# SparkFun_MOSFET_Power_Switch.net
KiCad netlist of a schematic drawn in EAGLE
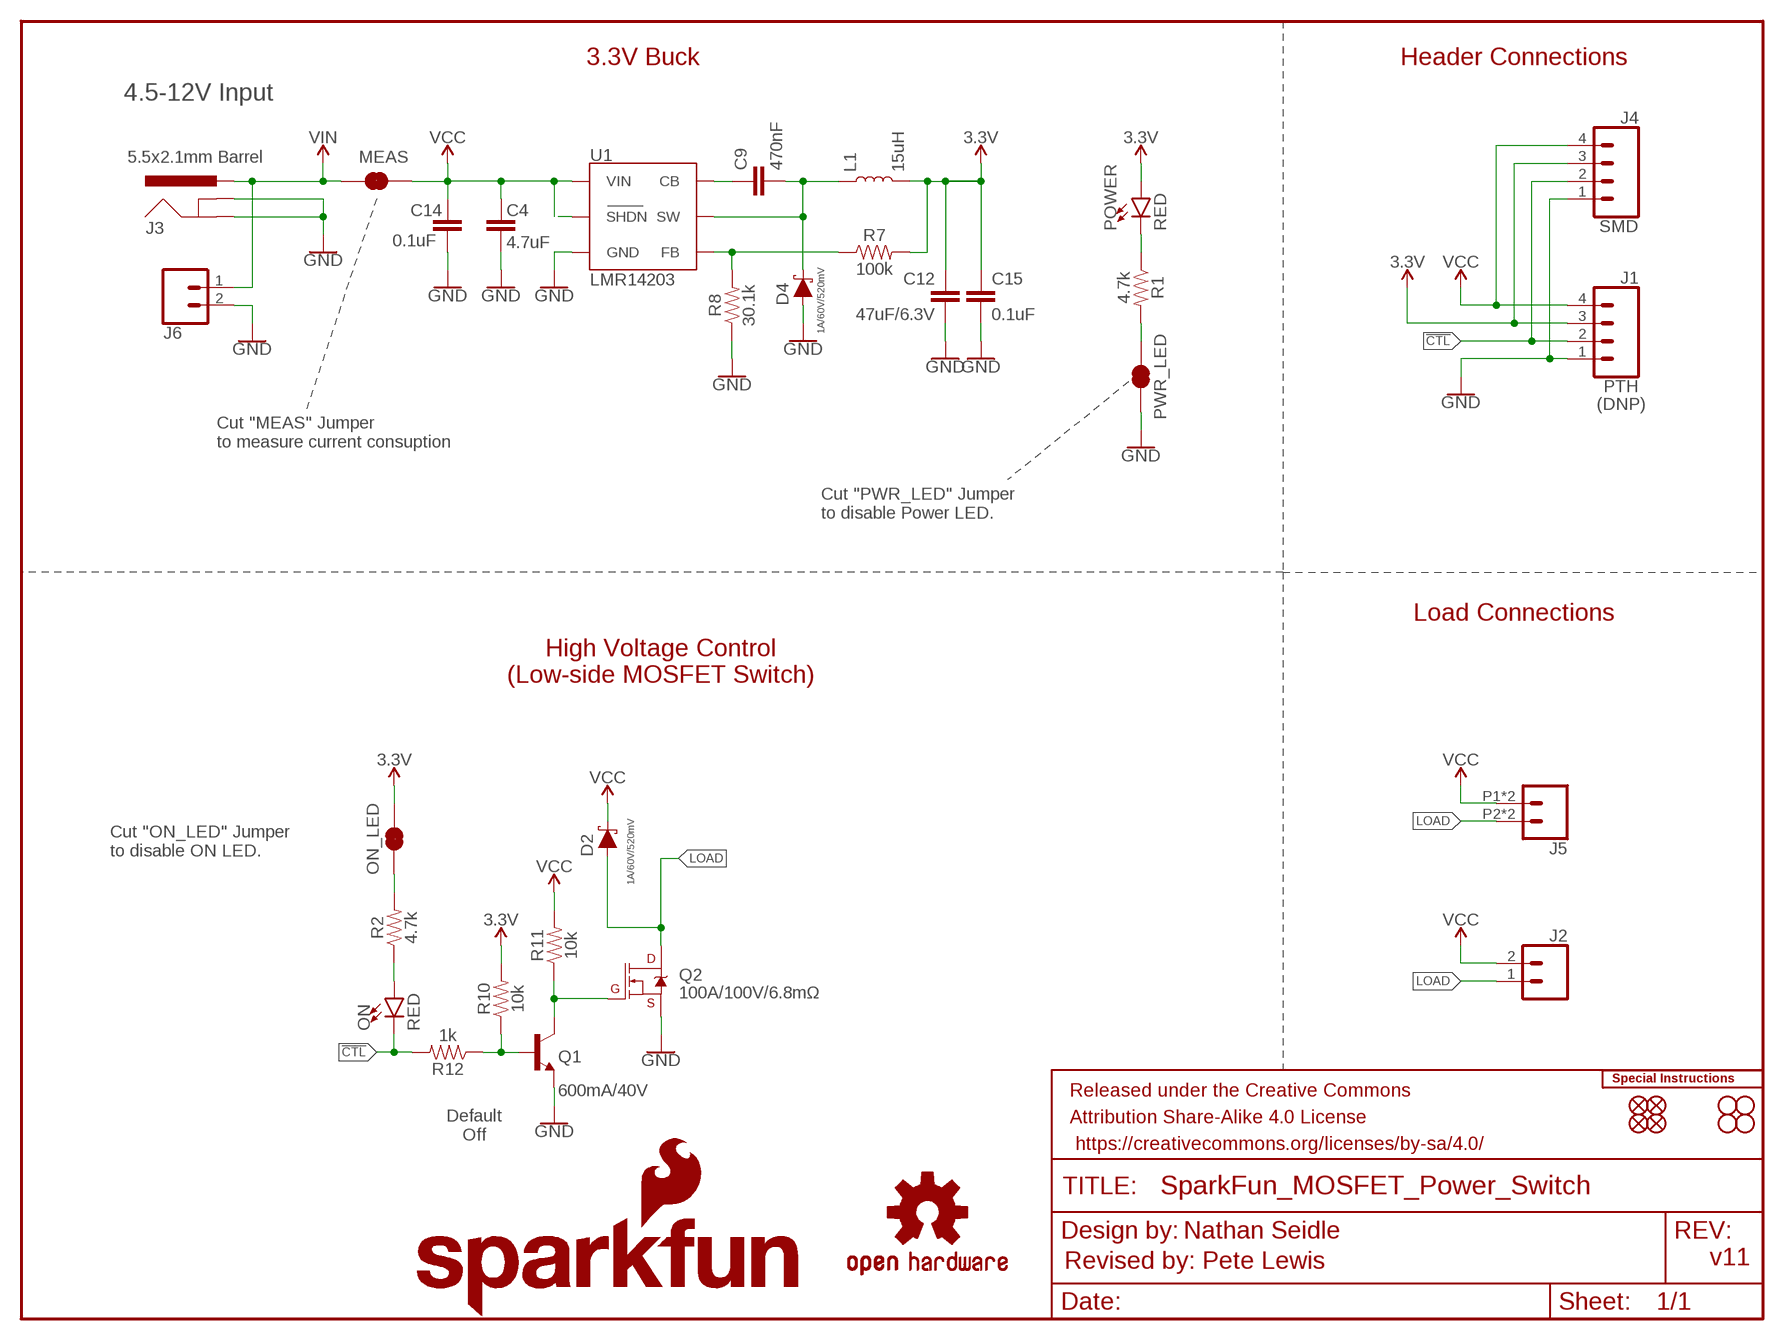
[diagram p0: schematic, sheet 1]

(export (version "E")
  (design (tool "Eeschema 10.0.6"))
  (components
    (comp (ref "C4")
      (value "4.7uF")
      (footprint "eagle-import:0603")
      (libsource (lib "eagle-import") (part "4.7UF-0603-35V-(20%)"))
    )
    (comp (ref "C9")
      (value "470nF")
      (footprint "eagle-import:0603")
      (libsource (lib "eagle-import") (part "470NF-0603-10V-10%-X5R"))
    )
    (comp (ref "C12")
      (value "47uF/6.3V")
      (footprint "eagle-import:0805")
      (libsource (lib "eagle-import") (part "47UF"))
    )
    (comp (ref "C14")
      (value "0.1uF")
      (footprint "eagle-import:0603")
      (libsource (lib "eagle-import") (part "0.1UF-0603-100V-10%"))
    )
    (comp (ref "C15")
      (value "0.1uF")
      (footprint "eagle-import:0603")
      (libsource (lib "eagle-import") (part "0.1UF-0603-100V-10%"))
    )
    (comp (ref "D2")
      (value "1A/60V/520mV")
      (footprint "eagle-import:DIODE-MICRO-SMP")
      (libsource (lib "eagle-import") (part "DIODE-SCHOTTKY-MSS1P6-M3/89A"))
    )
    (comp (ref "D4")
      (value "1A/60V/520mV")
      (footprint "eagle-import:DIODE-MICRO-SMP")
      (libsource (lib "eagle-import") (part "DIODE-SCHOTTKY-MSS1P6-M3/89A"))
    )
    (comp (ref "FD1")
      (value "FIDUCIALUFIDUCIAL")
      (footprint "eagle-import:FIDUCIAL-MICRO")
      (libsource (lib "eagle-import") (part "FIDUCIALUFIDUCIAL"))
    )
    (comp (ref "FD2")
      (value "FIDUCIALUFIDUCIAL")
      (footprint "eagle-import:FIDUCIAL-MICRO")
      (libsource (lib "eagle-import") (part "FIDUCIALUFIDUCIAL"))
    )
    (comp (ref "FD3")
      (value "FIDUCIALUFIDUCIAL")
      (footprint "eagle-import:FIDUCIAL-MICRO")
      (libsource (lib "eagle-import") (part "FIDUCIALUFIDUCIAL"))
    )
    (comp (ref "FD4")
      (value "FIDUCIALUFIDUCIAL")
      (footprint "eagle-import:FIDUCIAL-MICRO")
      (libsource (lib "eagle-import") (part "FIDUCIALUFIDUCIAL"))
    )
    (comp (ref "FRAME2")
      (value "FRAME-LETTER")
      (footprint "eagle-import:CREATIVE_COMMONS")
      (libsource (lib "eagle-import") (part "FRAME-LETTER"))
    )
    (comp (ref "H1")
      (value "STAND-OFF")
      (footprint "eagle-import:STAND-OFF")
      (libsource (lib "eagle-import") (part "STAND-OFF"))
    )
    (comp (ref "H2")
      (value "STAND-OFF")
      (footprint "eagle-import:STAND-OFF")
      (libsource (lib "eagle-import") (part "STAND-OFF"))
    )
    (comp (ref "H3")
      (value "STAND-OFF")
      (footprint "eagle-import:STAND-OFF")
      (libsource (lib "eagle-import") (part "STAND-OFF"))
    )
    (comp (ref "H4")
      (value "STAND-OFF")
      (footprint "eagle-import:STAND-OFF")
      (libsource (lib "eagle-import") (part "STAND-OFF"))
    )
    (comp (ref "J1")
      (value "PTH")
      (footprint "eagle-import:1X04_NO_SILK")
      (libsource (lib "eagle-import") (part "CONN_041X04_NO_SILK_NO_POP"))
    )
    (comp (ref "J2")
      (value "CONN_021X02_NO_SILK")
      (footprint "eagle-import:1X02_NO_SILK")
      (libsource (lib "eagle-import") (part "CONN_021X02_NO_SILK"))
    )
    (comp (ref "J3")
      (value "5.5x2.1mm Barrel")
      (footprint "eagle-import:POWER_JACK_SMD")
      (libsource (lib "eagle-import") (part "POWER_JACKSMD"))
    )
    (comp (ref "J4")
      (value "SMD")
      (footprint "eagle-import:1X04_SMD_VERTICAL_COMBO")
      (libsource (lib "eagle-import") (part "CONN_04SMD_STRAIGHT_COMBO"))
    )
    (comp (ref "J5")
      (value "CONN_02SMALL_POKEHOME")
      (footprint "eagle-import:1X02_POKEHOME")
      (libsource (lib "eagle-import") (part "CONN_02SMALL_POKEHOME"))
    )
    (comp (ref "J6")
      (value "CONN_021X02_NO_SILK")
      (footprint "eagle-import:1X02_NO_SILK")
      (libsource (lib "eagle-import") (part "CONN_021X02_NO_SILK"))
    )
    (comp (ref "L1")
      (value "15uH")
      (footprint "eagle-import:INDUCTOR_LQH32")
      (libsource (lib "eagle-import") (part "INDUCTOR-LHQ32-15UH"))
    )
    (comp (ref "LOGO1")
      (value "OSHW-LOGOM")
      (footprint "eagle-import:OSHW-LOGO-M")
      (libsource (lib "eagle-import") (part "OSHW-LOGOM"))
    )
    (comp (ref "LOGO2")
      (value "SFE_LOGO_NAME_FLAME.2_INCH")
      (footprint "eagle-import:SFE_LOGO_NAME_FLAME_.2")
      (libsource (lib "eagle-import") (part "SFE_LOGO_NAME_FLAME.2_INCH"))
    )
    (comp (ref "LOGO3")
      (value "SPECIAL_INSTRUCTIONS-ORDERING")
      (footprint "eagle-import:ORDERING_INSTRUCTIONS")
      (libsource (lib "eagle-import") (part "SPECIAL_INSTRUCTIONS-ORDERING"))
    )
    (comp (ref "MEAS")
      (value "JUMPER-COMBO_2_NC_TRACE")
      (footprint "eagle-import:COMBO-JUMPER_2_NC_TRACE")
      (libsource (lib "eagle-import") (part "JUMPER-COMBO_2_NC_TRACE"))
    )
    (comp (ref "ON")
      (value "RED")
      (footprint "eagle-import:LED-0603")
      (libsource (lib "eagle-import") (part "LED-RED_0603-KB"))
    )
    (comp (ref "ON_LED")
      (value "JUMPER-SMT_2_NC_TRACE_SILK")
      (footprint "eagle-import:SMT-JUMPER_2_NC_TRACE_SILK")
      (libsource (lib "eagle-import") (part "JUMPER-SMT_2_NC_TRACE_SILK"))
    )
    (comp (ref "POWER")
      (value "RED")
      (footprint "eagle-import:LED-0603")
      (libsource (lib "eagle-import") (part "LED-RED_0603-KB"))
    )
    (comp (ref "PWR_LED")
      (value "JUMPER-SMT_2_NC_TRACE_SILK")
      (footprint "eagle-import:SMT-JUMPER_2_NC_TRACE_SILK")
      (libsource (lib "eagle-import") (part "JUMPER-SMT_2_NC_TRACE_SILK"))
    )
    (comp (ref "Q1")
      (value "600mA/40V")
      (footprint "eagle-import:SOT23-3")
      (libsource (lib "eagle-import") (part "TRANS_NPN-MMBT2222AL"))
    )
    (comp (ref "Q2")
      (value "100A/100V/6.8mΩ")
      (footprint "eagle-import:TO-263_D2PAK")
      (libsource (lib "eagle-import") (part "MOSFET-NCH-PSMN7R0"))
    )
    (comp (ref "R1")
      (value "4.7k")
      (footprint "eagle-import:0603")
      (libsource (lib "eagle-import") (part "4.7KOHM-0603-1/10W-1%"))
    )
    (comp (ref "R2")
      (value "4.7k")
      (footprint "eagle-import:0603")
      (libsource (lib "eagle-import") (part "4.7KOHM-0603-1/10W-1%"))
    )
    (comp (ref "R7")
      (value "100k")
      (footprint "eagle-import:0603")
      (libsource (lib "eagle-import") (part "100KOHM-0603-1/10W-1%"))
    )
    (comp (ref "R8")
      (value "30.1k")
      (footprint "eagle-import:0603")
      (libsource (lib "eagle-import") (part "30.1KOHM-0603-1/10W-1%"))
    )
    (comp (ref "R10")
      (value "10k")
      (footprint "eagle-import:0603")
      (libsource (lib "eagle-import") (part "10KOHM-0603-1/10W-1%"))
    )
    (comp (ref "R11")
      (value "10k")
      (footprint "eagle-import:0603")
      (libsource (lib "eagle-import") (part "10KOHM-0603-1/10W-1%"))
    )
    (comp (ref "R12")
      (value "1k")
      (footprint "eagle-import:0603")
      (libsource (lib "eagle-import") (part "1KOHM-0603-1/10W-1%"))
    )
    (comp (ref "U1")
      (value "LMR14203")
      (footprint "eagle-import:SOT23-6")
      (libsource (lib "eagle-import") (part "LMR14203"))
    )
  )
  (nets
    (net (code "1") (name "/~{CTL}") (class "Default")
      (node (ref "J1") (pin "2") (pinfunction "2_2") (pintype "passive"))
      (node (ref "J4") (pin "2") (pinfunction "2_2") (pintype "passive"))
      (node (ref "ON") (pin "C") (pinfunction "C_C") (pintype "passive"))
      (node (ref "R12") (pin "2") (pinfunction "2_2") (pintype "passive"))
    )
    (net (code "2") (name "3.3V") (class "Default")
      (node (ref "C12") (pin "1") (pinfunction "1_1") (pintype "passive"))
      (node (ref "C15") (pin "1") (pinfunction "1_1") (pintype "passive"))
      (node (ref "J1") (pin "3") (pinfunction "3_3") (pintype "passive"))
      (node (ref "J4") (pin "3") (pinfunction "3_3") (pintype "passive"))
      (node (ref "L1") (pin "P$2") (pinfunction "2_P$2") (pintype "passive"))
      (node (ref "ON_LED") (pin "2") (pinfunction "2_2") (pintype "passive"))
      (node (ref "POWER") (pin "A") (pinfunction "A_A") (pintype "passive"))
      (node (ref "R10") (pin "2") (pinfunction "2_2") (pintype "passive"))
      (node (ref "R7") (pin "2") (pinfunction "2_2") (pintype "passive"))
    )
    (net (code "3") (name "GND") (class "Default")
      (node (ref "C12") (pin "2") (pinfunction "2_2") (pintype "passive"))
      (node (ref "C14") (pin "2") (pinfunction "2_2") (pintype "passive"))
      (node (ref "C15") (pin "2") (pinfunction "2_2") (pintype "passive"))
      (node (ref "C4") (pin "2") (pinfunction "2_2") (pintype "passive"))
      (node (ref "D4") (pin "A") (pinfunction "A_A") (pintype "passive"))
      (node (ref "J1") (pin "1") (pinfunction "1_1") (pintype "passive"))
      (node (ref "J3") (pin "GND") (pinfunction "GNDBREAK_GND") (pintype "bidirectional"))
      (node (ref "J3") (pin "P$4") (pinfunction "GND_P$4") (pintype "bidirectional"))
      (node (ref "J4") (pin "1") (pinfunction "1_1") (pintype "passive"))
      (node (ref "J6") (pin "2") (pinfunction "2_2") (pintype "passive"))
      (node (ref "PWR_LED") (pin "1") (pinfunction "1_1") (pintype "passive"))
      (node (ref "Q1") (pin "2") (pinfunction "E_2") (pintype "passive"))
      (node (ref "Q2") (pin "3") (pinfunction "S_3") (pintype "bidirectional"))
      (node (ref "R8") (pin "1") (pinfunction "1_1") (pintype "passive"))
      (node (ref "U1") (pin "2") (pinfunction "GND_2") (pintype "power_in"))
    )
    (net (code "4") (name "LOAD") (class "Default")
      (node (ref "D2") (pin "A") (pinfunction "A_A") (pintype "passive"))
      (node (ref "J2") (pin "1") (pinfunction "1_1") (pintype "passive"))
      (node (ref "J5") (pin "P2") (pinfunction "2_P2") (pintype "passive"))
      (node (ref "J5") (pin "P4") (pinfunction "2_P4") (pintype "passive"))
      (node (ref "Q2") (pin "2") (pinfunction "D_2") (pintype "bidirectional"))
    )
    (net (code "5") (name "Net-(L1-1)") (class "Default")
      (node (ref "C9") (pin "2") (pinfunction "2_2") (pintype "passive"))
      (node (ref "D4") (pin "C") (pinfunction "C_C") (pintype "passive"))
      (node (ref "L1") (pin "P$1") (pinfunction "1_P$1") (pintype "passive"))
      (node (ref "U1") (pin "6") (pinfunction "SW_6") (pintype "power_in"))
    )
    (net (code "6") (name "Net-(ON-PadA)") (class "Default")
      (node (ref "ON") (pin "A") (pinfunction "A_A") (pintype "passive"))
      (node (ref "R2") (pin "1") (pinfunction "1_1") (pintype "passive"))
    )
    (net (code "7") (name "Net-(ON_LED-Pad1)") (class "Default")
      (node (ref "ON_LED") (pin "1") (pinfunction "1_1") (pintype "passive"))
      (node (ref "R2") (pin "2") (pinfunction "2_2") (pintype "passive"))
    )
    (net (code "8") (name "Net-(POWER-PadC)") (class "Default")
      (node (ref "POWER") (pin "C") (pinfunction "C_C") (pintype "passive"))
      (node (ref "R1") (pin "1") (pinfunction "1_1") (pintype "passive"))
    )
    (net (code "9") (name "Net-(PWR_LED-Pad2)") (class "Default")
      (node (ref "PWR_LED") (pin "2") (pinfunction "2_2") (pintype "passive"))
      (node (ref "R1") (pin "2") (pinfunction "2_2") (pintype "passive"))
    )
    (net (code "10") (name "Net-(Q1-B)") (class "Default")
      (node (ref "Q1") (pin "1") (pinfunction "B_1") (pintype "passive"))
      (node (ref "R10") (pin "1") (pinfunction "1_1") (pintype "passive"))
      (node (ref "R12") (pin "1") (pinfunction "1_1") (pintype "passive"))
    )
    (net (code "11") (name "Net-(Q1-C)") (class "Default")
      (node (ref "Q1") (pin "3") (pinfunction "C_3") (pintype "passive"))
      (node (ref "Q2") (pin "1") (pinfunction "G_1") (pintype "bidirectional"))
      (node (ref "R11") (pin "1") (pinfunction "1_1") (pintype "passive"))
    )
    (net (code "12") (name "Net-(U1-CB)") (class "Default")
      (node (ref "C9") (pin "1") (pinfunction "1_1") (pintype "passive"))
      (node (ref "U1") (pin "1") (pinfunction "CB_1") (pintype "input"))
    )
    (net (code "13") (name "Net-(U1-FB)") (class "Default")
      (node (ref "R7") (pin "1") (pinfunction "1_1") (pintype "passive"))
      (node (ref "R8") (pin "2") (pinfunction "2_2") (pintype "passive"))
      (node (ref "U1") (pin "3") (pinfunction "FB_3") (pintype "input"))
    )
    (net (code "14") (name "VCC") (class "Default")
      (node (ref "C14") (pin "1") (pinfunction "1_1") (pintype "passive"))
      (node (ref "C4") (pin "1") (pinfunction "1_1") (pintype "passive"))
      (node (ref "D2") (pin "C") (pinfunction "C_C") (pintype "passive"))
      (node (ref "J1") (pin "4") (pinfunction "4_4") (pintype "passive"))
      (node (ref "J2") (pin "2") (pinfunction "2_2") (pintype "passive"))
      (node (ref "J4") (pin "4") (pinfunction "4_4") (pintype "passive"))
      (node (ref "J5") (pin "P1") (pinfunction "1_P1") (pintype "passive"))
      (node (ref "J5") (pin "P3") (pinfunction "1_P3") (pintype "passive"))
      (node (ref "MEAS") (pin "2") (pinfunction "2_2") (pintype "passive"))
      (node (ref "MEAS") (pin "4") (pinfunction "2_4") (pintype "passive"))
      (node (ref "R11") (pin "2") (pinfunction "2_2") (pintype "passive"))
      (node (ref "U1") (pin "4") (pinfunction "SHDN_4") (pintype "input"))
      (node (ref "U1") (pin "5") (pinfunction "VIN_5") (pintype "power_in"))
    )
    (net (code "15") (name "VIN") (class "Default")
      (node (ref "J3") (pin "VIN0") (pinfunction "PWR_VIN0") (pintype "bidirectional"))
      (node (ref "J6") (pin "1") (pinfunction "1_1") (pintype "passive"))
      (node (ref "MEAS") (pin "1") (pinfunction "1_1") (pintype "passive"))
      (node (ref "MEAS") (pin "3") (pinfunction "1_3") (pintype "passive"))
    )
  )
)
